# Stick1_jr1.net
KiCad netlist of a schematic drawn in EAGLE
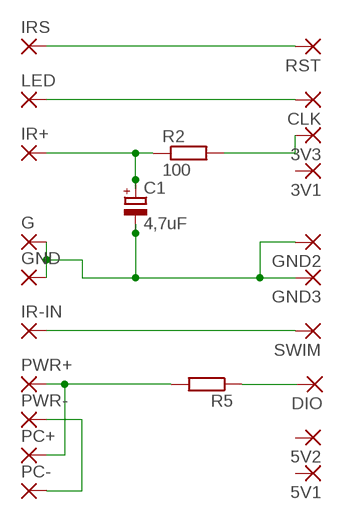
[diagram p0: schematic, sheet 1]

(export (version "E")
  (design (tool "Eeschema 10.0.6"))
  (components
    (comp (ref "3V1")
      (value "SMD2")
      (footprint "eagle-import:SMD1,27-2,54")
      (libsource (lib "eagle-import") (part "SMD2"))
    )
    (comp (ref "3V3")
      (value "SMD2")
      (footprint "eagle-import:SMD1,27-2,54")
      (libsource (lib "eagle-import") (part "SMD2"))
    )
    (comp (ref "5V1")
      (value "SMD2")
      (footprint "eagle-import:SMD1,27-2,54")
      (libsource (lib "eagle-import") (part "SMD2"))
    )
    (comp (ref "5V2")
      (value "SMD2")
      (footprint "eagle-import:SMD1,27-2,54")
      (libsource (lib "eagle-import") (part "SMD2"))
    )
    (comp (ref "C1")
      (value "4,7uF")
      (footprint "eagle-import:E1,8-4")
      (libsource (lib "eagle-import") (part "CPOL-EUE1.8-4"))
    )
    (comp (ref "CLK")
      (value "SMD2")
      (footprint "eagle-import:SMD1,27-2,54")
      (libsource (lib "eagle-import") (part "SMD2"))
    )
    (comp (ref "DIO")
      (value "SMD2")
      (footprint "eagle-import:SMD1,27-2,54")
      (libsource (lib "eagle-import") (part "SMD2"))
    )
    (comp (ref "G")
      (value "SMD2")
      (footprint "eagle-import:SMD1,27-2,54")
      (libsource (lib "eagle-import") (part "SMD2"))
    )
    (comp (ref "GND")
      (value "SMD2")
      (footprint "eagle-import:SMD1,27-2,54")
      (libsource (lib "eagle-import") (part "SMD2"))
    )
    (comp (ref "GND2")
      (value "SMD2")
      (footprint "eagle-import:SMD1,27-2,54")
      (libsource (lib "eagle-import") (part "SMD2"))
    )
    (comp (ref "GND3")
      (value "SMD2")
      (footprint "eagle-import:SMD1,27-2,54")
      (libsource (lib "eagle-import") (part "SMD2"))
    )
    (comp (ref "IR+")
      (value "SMD2")
      (footprint "eagle-import:SMD1,27-2,54")
      (libsource (lib "eagle-import") (part "SMD2"))
    )
    (comp (ref "IR-IN")
      (value "SMD2")
      (footprint "eagle-import:SMD1,27-2,54")
      (libsource (lib "eagle-import") (part "SMD2"))
    )
    (comp (ref "IRS")
      (value "SMD2")
      (footprint "eagle-import:SMD1,27-2,54")
      (libsource (lib "eagle-import") (part "SMD2"))
    )
    (comp (ref "LED")
      (value "SMD2")
      (footprint "eagle-import:SMD1,27-2,54")
      (libsource (lib "eagle-import") (part "SMD2"))
    )
    (comp (ref "PC+")
      (value "SMD2")
      (footprint "eagle-import:SMD1,27-2,54")
      (libsource (lib "eagle-import") (part "SMD2"))
    )
    (comp (ref "PC-")
      (value "SMD2")
      (footprint "eagle-import:SMD1,27-2,54")
      (libsource (lib "eagle-import") (part "SMD2"))
    )
    (comp (ref "PWR+")
      (value "SMD2")
      (footprint "eagle-import:SMD1,27-2,54")
      (libsource (lib "eagle-import") (part "SMD2"))
    )
    (comp (ref "PWR-")
      (value "SMD2")
      (footprint "eagle-import:SMD1,27-2,54")
      (libsource (lib "eagle-import") (part "SMD2"))
    )
    (comp (ref "R2")
      (value "100")
      (footprint "eagle-import:0204_7")
      (libsource (lib "eagle-import") (part "R-EU_0204/7"))
    )
    (comp (ref "R5")
      (value "R-EU_0204/7")
      (footprint "eagle-import:0204_7")
      (libsource (lib "eagle-import") (part "R-EU_0204/7"))
    )
    (comp (ref "RST")
      (value "SMD2")
      (footprint "eagle-import:SMD1,27-2,54")
      (libsource (lib "eagle-import") (part "SMD2"))
    )
    (comp (ref "SWIM")
      (value "SMD2")
      (footprint "eagle-import:SMD1,27-2,54")
      (libsource (lib "eagle-import") (part "SMD2"))
    )
  )
  (nets
    (net (code "1") (name "Net-(3V3-P)") (class "Default")
      (node (ref "3V3") (pin "1") (pinfunction "P_1") (pintype "passive"))
      (node (ref "R2") (pin "2") (pinfunction "2_2") (pintype "passive"))
    )
    (net (code "2") (name "Net-(CLK-P)") (class "Default")
      (node (ref "CLK") (pin "1") (pinfunction "P_1") (pintype "passive"))
      (node (ref "LED") (pin "1") (pinfunction "P_1") (pintype "passive"))
    )
    (net (code "3") (name "Net-(DIO-P)") (class "Default")
      (node (ref "DIO") (pin "1") (pinfunction "P_1") (pintype "passive"))
      (node (ref "R5") (pin "1") (pinfunction "1_1") (pintype "passive"))
    )
    (net (code "4") (name "Net-(G-P)") (class "Default")
      (node (ref "C1") (pin "-") (pinfunction "-_-") (pintype "passive"))
      (node (ref "G") (pin "1") (pinfunction "P_1") (pintype "passive"))
      (node (ref "GND") (pin "1") (pinfunction "P_1") (pintype "passive"))
      (node (ref "GND2") (pin "1") (pinfunction "P_1") (pintype "passive"))
      (node (ref "GND3") (pin "1") (pinfunction "P_1") (pintype "passive"))
    )
    (net (code "5") (name "Net-(IR+-P)") (class "Default")
      (node (ref "C1") (pin "+") (pinfunction "+_+") (pintype "passive"))
      (node (ref "IR+") (pin "1") (pinfunction "P_1") (pintype "passive"))
      (node (ref "R2") (pin "1") (pinfunction "1_1") (pintype "passive"))
    )
    (net (code "6") (name "Net-(IR-IN-P)") (class "Default")
      (node (ref "IR-IN") (pin "1") (pinfunction "P_1") (pintype "passive"))
      (node (ref "SWIM") (pin "1") (pinfunction "P_1") (pintype "passive"))
    )
    (net (code "7") (name "Net-(IRS-P)") (class "Default")
      (node (ref "IRS") (pin "1") (pinfunction "P_1") (pintype "passive"))
      (node (ref "RST") (pin "1") (pinfunction "P_1") (pintype "passive"))
    )
    (net (code "8") (name "Net-(PC+-P)") (class "Default")
      (node (ref "PC+") (pin "1") (pinfunction "P_1") (pintype "passive"))
      (node (ref "PWR+") (pin "1") (pinfunction "P_1") (pintype "passive"))
      (node (ref "R5") (pin "2") (pinfunction "2_2") (pintype "passive"))
    )
    (net (code "9") (name "Net-(PC--P)") (class "Default")
      (node (ref "PC-") (pin "1") (pinfunction "P_1") (pintype "passive"))
      (node (ref "PWR-") (pin "1") (pinfunction "P_1") (pintype "passive"))
    )
    (net (code "10") (name "unconnected-(3V1-P-Pad1)") (class "Default")
      (node (ref "3V1") (pin "1") (pinfunction "P_1") (pintype "passive"))
    )
    (net (code "11") (name "unconnected-(5V1-P-Pad1)") (class "Default")
      (node (ref "5V1") (pin "1") (pinfunction "P_1") (pintype "passive"))
    )
    (net (code "12") (name "unconnected-(5V2-P-Pad1)") (class "Default")
      (node (ref "5V2") (pin "1") (pinfunction "P_1") (pintype "passive"))
    )
  )
)
